# PowerBoard-v1_2.net
KiCad netlist of a schematic drawn in EAGLE
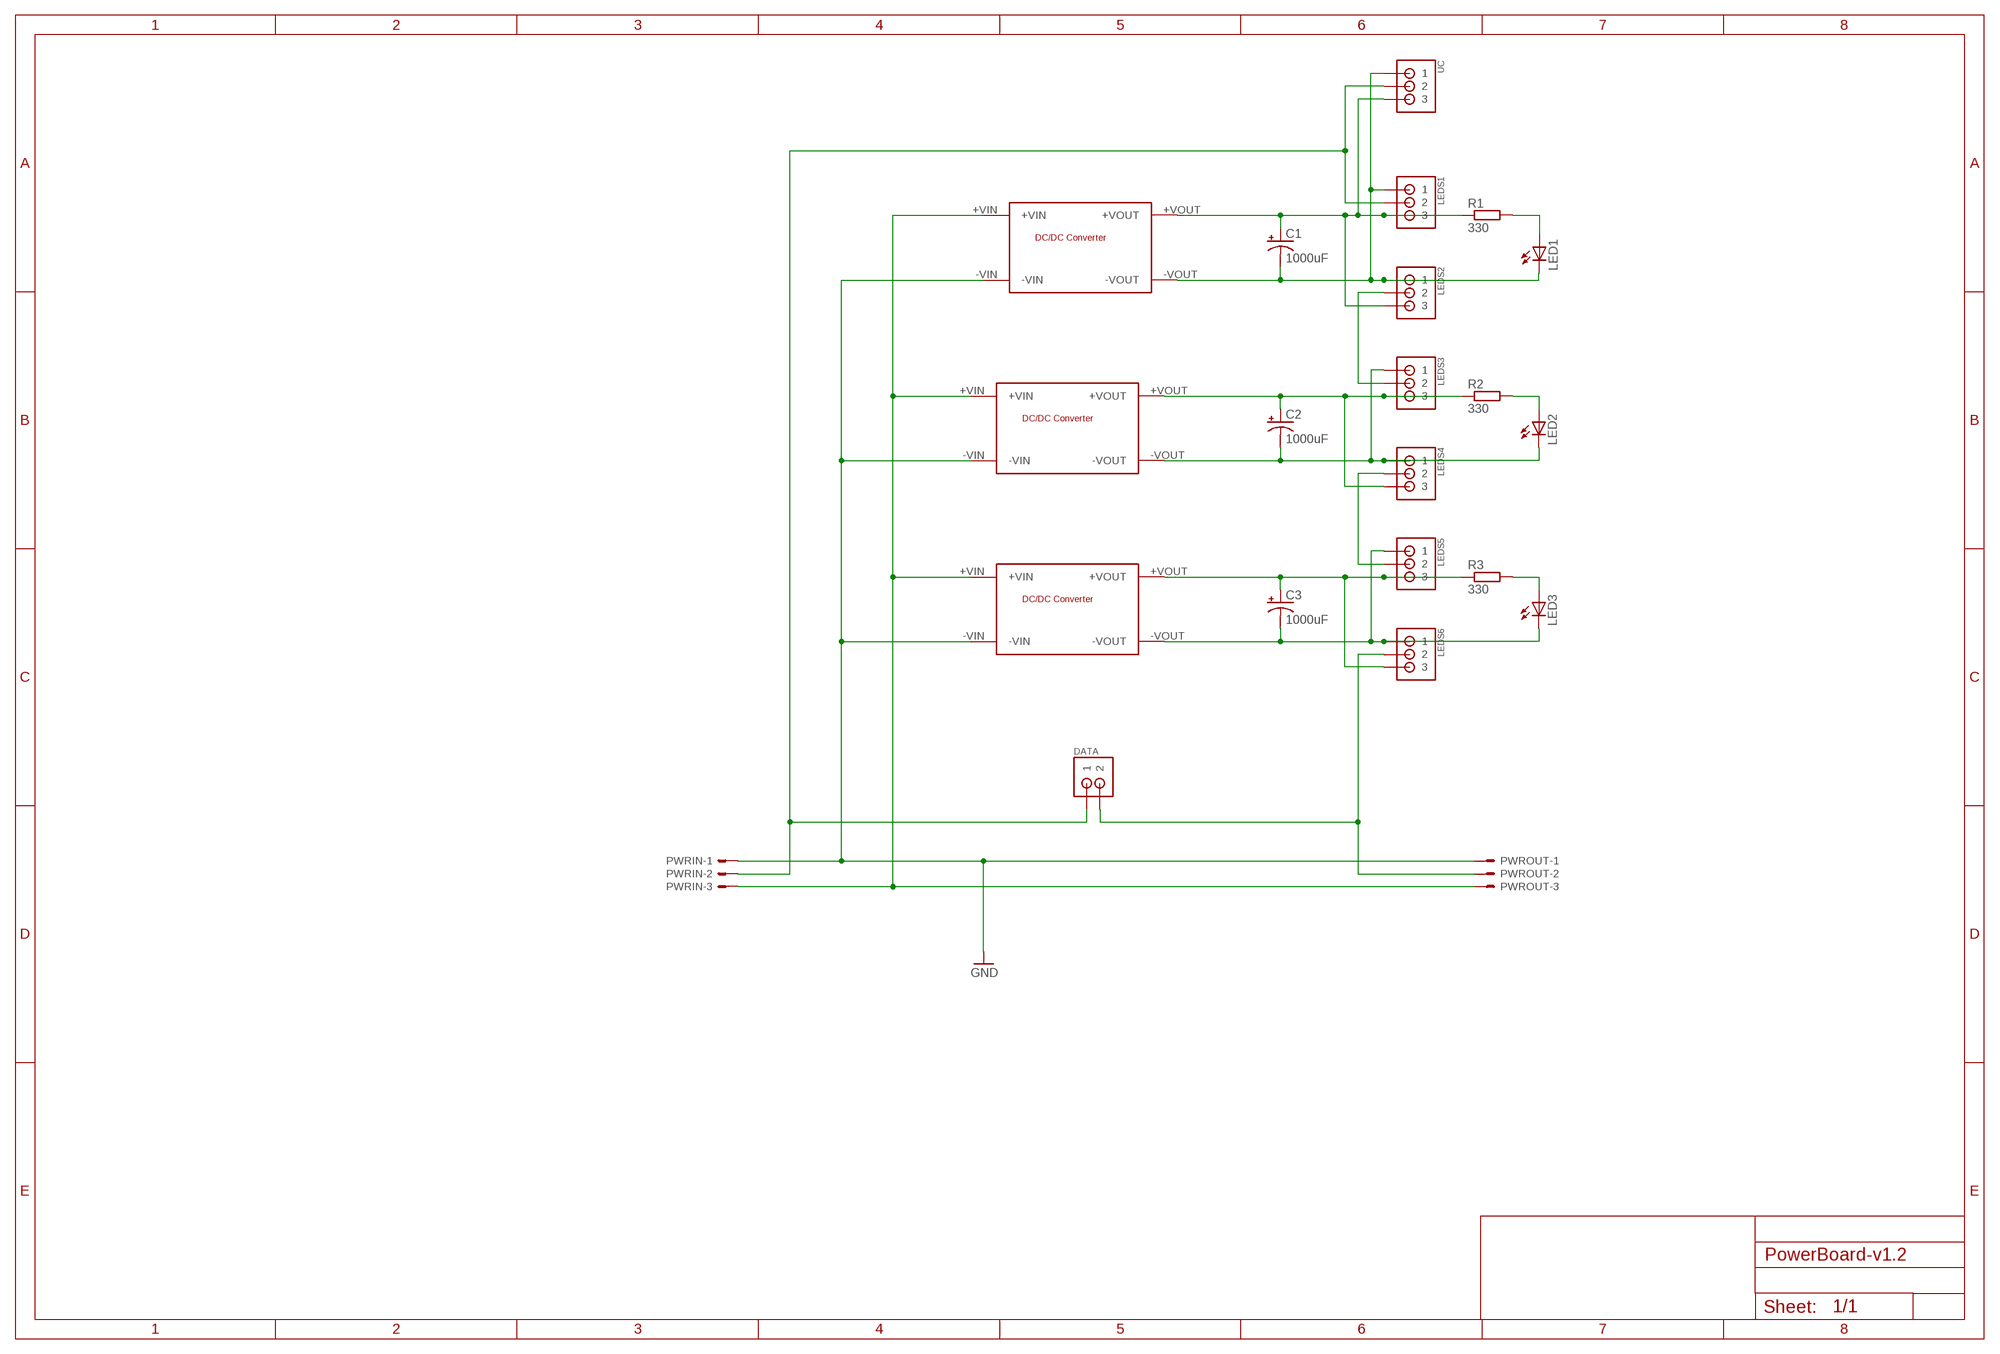
[diagram p0: schematic, sheet 1]

(export (version "E")
  (design (tool "Eeschema 10.0.6"))
  (components
    (comp (ref "C1")
      (value "1000uF")
      (footprint "eagle-import:CPOL-RADIAL-1000UF-25V")
      (libsource (lib "eagle-import") (part "CAP_POLPTH4"))
    )
    (comp (ref "C2")
      (value "1000uF")
      (footprint "eagle-import:CPOL-RADIAL-1000UF-25V")
      (libsource (lib "eagle-import") (part "CAP_POLPTH4"))
    )
    (comp (ref "C3")
      (value "1000uF")
      (footprint "eagle-import:CPOL-RADIAL-1000UF-25V")
      (libsource (lib "eagle-import") (part "CAP_POLPTH4"))
    )
    (comp (ref "DATA")
      (value "JST-XA-02-PIN")
      (footprint "eagle-import:JST-XA-02")
      (libsource (lib "eagle-import") (part "JST-XA-02-PIN"))
    )
    (comp (ref "LED1")
      (value "LEDCHIP-LED0805")
      (footprint "eagle-import:CHIP-LED0805")
      (libsource (lib "eagle-import") (part "LEDCHIP-LED0805"))
    )
    (comp (ref "LED2")
      (value "LEDCHIP-LED0805")
      (footprint "eagle-import:CHIP-LED0805")
      (libsource (lib "eagle-import") (part "LEDCHIP-LED0805"))
    )
    (comp (ref "LED3")
      (value "LEDCHIP-LED0805")
      (footprint "eagle-import:CHIP-LED0805")
      (libsource (lib "eagle-import") (part "LEDCHIP-LED0805"))
    )
    (comp (ref "LEDS1")
      (value "JST-XA-03-PIN")
      (footprint "eagle-import:JST-XA-03")
      (libsource (lib "eagle-import") (part "JST-XA-03-PIN"))
    )
    (comp (ref "LEDS2")
      (value "JST-XA-03-PIN")
      (footprint "eagle-import:JST-XA-03")
      (libsource (lib "eagle-import") (part "JST-XA-03-PIN"))
    )
    (comp (ref "LEDS3")
      (value "JST-XA-03-PIN")
      (footprint "eagle-import:JST-XA-03")
      (libsource (lib "eagle-import") (part "JST-XA-03-PIN"))
    )
    (comp (ref "LEDS4")
      (value "JST-XA-03-PIN")
      (footprint "eagle-import:JST-XA-03")
      (libsource (lib "eagle-import") (part "JST-XA-03-PIN"))
    )
    (comp (ref "LEDS5")
      (value "JST-XA-03-PIN")
      (footprint "eagle-import:JST-XA-03")
      (libsource (lib "eagle-import") (part "JST-XA-03-PIN"))
    )
    (comp (ref "LEDS6")
      (value "JST-XA-03-PIN")
      (footprint "eagle-import:JST-XA-03")
      (libsource (lib "eagle-import") (part "JST-XA-03-PIN"))
    )
    (comp (ref "PWRIN")
      (value "KK-156-3")
      (footprint "eagle-import:KK-156-3")
      (fields (field (name "MF") "MOLEX"))
      (libsource (lib "eagle-import") (part "KK-156-3"))
    )
    (comp (ref "PWROUT")
      (value "KK-156-3")
      (footprint "eagle-import:KK-156-3")
      (fields (field (name "MF") "MOLEX"))
      (libsource (lib "eagle-import") (part "KK-156-3"))
    )
    (comp (ref "R1")
      (value "330")
      (footprint "eagle-import:M0805")
      (libsource (lib "eagle-import") (part "RESISTORM0805"))
    )
    (comp (ref "R2")
      (value "330")
      (footprint "eagle-import:M0805")
      (libsource (lib "eagle-import") (part "RESISTORM0805"))
    )
    (comp (ref "R3")
      (value "330")
      (footprint "eagle-import:M0805")
      (libsource (lib "eagle-import") (part "RESISTORM0805"))
    )
    (comp (ref "U$1")
      (value "DC-DC-CONVERTER")
      (footprint "eagle-import:MP1584EN-BUCK-CONVERTER")
      (libsource (lib "eagle-import") (part "DC-DC-CONVERTER"))
    )
    (comp (ref "U$2")
      (value "DC-DC-CONVERTER")
      (footprint "eagle-import:MP1584EN-BUCK-CONVERTER")
      (libsource (lib "eagle-import") (part "DC-DC-CONVERTER"))
    )
    (comp (ref "U$3")
      (value "DC-DC-CONVERTER")
      (footprint "eagle-import:MP1584EN-BUCK-CONVERTER")
      (libsource (lib "eagle-import") (part "DC-DC-CONVERTER"))
    )
    (comp (ref "UC")
      (value "JST-XA-03-PIN")
      (footprint "eagle-import:JST-XA-03")
      (libsource (lib "eagle-import") (part "JST-XA-03-PIN"))
    )
  )
  (nets
    (net (code "1") (name "GND") (class "Default")
      (node (ref "PWRIN") (pin "1") (pinfunction "S_1") (pintype "passive"))
      (node (ref "PWROUT") (pin "1") (pinfunction "S_1") (pintype "passive"))
      (node (ref "U$1") (pin "-VIN") (pinfunction "-VIN_-VIN") (pintype "bidirectional"))
      (node (ref "U$2") (pin "-VIN") (pinfunction "-VIN_-VIN") (pintype "bidirectional"))
      (node (ref "U$3") (pin "-VIN") (pinfunction "-VIN_-VIN") (pintype "bidirectional"))
    )
    (net (code "2") (name "Net-(C1-Pad+)") (class "Default")
      (node (ref "C1") (pin "+") (pinfunction "+_+") (pintype "passive"))
      (node (ref "LEDS1") (pin "3") (pinfunction "3_3") (pintype "bidirectional"))
      (node (ref "LEDS2") (pin "3") (pinfunction "3_3") (pintype "bidirectional"))
      (node (ref "R1") (pin "1") (pinfunction "1_1") (pintype "passive"))
      (node (ref "U$1") (pin "+VOUT") (pinfunction "+VOUT_+VOUT") (pintype "bidirectional"))
      (node (ref "UC") (pin "3") (pinfunction "3_3") (pintype "bidirectional"))
    )
    (net (code "3") (name "Net-(C1-Pad-)") (class "Default")
      (node (ref "C1") (pin "-") (pinfunction "-_-") (pintype "passive"))
      (node (ref "LED1") (pin "C") (pinfunction "C_C") (pintype "passive"))
      (node (ref "LEDS1") (pin "1") (pinfunction "1_1") (pintype "bidirectional"))
      (node (ref "LEDS2") (pin "1") (pinfunction "1_1") (pintype "bidirectional"))
      (node (ref "U$1") (pin "-VOUT") (pinfunction "-VOUT_-VOUT") (pintype "bidirectional"))
      (node (ref "UC") (pin "1") (pinfunction "1_1") (pintype "bidirectional"))
    )
    (net (code "4") (name "Net-(C2-Pad+)") (class "Default")
      (node (ref "C2") (pin "+") (pinfunction "+_+") (pintype "passive"))
      (node (ref "LEDS3") (pin "3") (pinfunction "3_3") (pintype "bidirectional"))
      (node (ref "LEDS4") (pin "3") (pinfunction "3_3") (pintype "bidirectional"))
      (node (ref "R2") (pin "1") (pinfunction "1_1") (pintype "passive"))
      (node (ref "U$2") (pin "+VOUT") (pinfunction "+VOUT_+VOUT") (pintype "bidirectional"))
    )
    (net (code "5") (name "Net-(C2-Pad-)") (class "Default")
      (node (ref "C2") (pin "-") (pinfunction "-_-") (pintype "passive"))
      (node (ref "LED2") (pin "C") (pinfunction "C_C") (pintype "passive"))
      (node (ref "LEDS3") (pin "1") (pinfunction "1_1") (pintype "bidirectional"))
      (node (ref "LEDS4") (pin "1") (pinfunction "1_1") (pintype "bidirectional"))
      (node (ref "U$2") (pin "-VOUT") (pinfunction "-VOUT_-VOUT") (pintype "bidirectional"))
    )
    (net (code "6") (name "Net-(C3-Pad+)") (class "Default")
      (node (ref "C3") (pin "+") (pinfunction "+_+") (pintype "passive"))
      (node (ref "LEDS5") (pin "3") (pinfunction "3_3") (pintype "bidirectional"))
      (node (ref "LEDS6") (pin "3") (pinfunction "3_3") (pintype "bidirectional"))
      (node (ref "R3") (pin "1") (pinfunction "1_1") (pintype "passive"))
      (node (ref "U$3") (pin "+VOUT") (pinfunction "+VOUT_+VOUT") (pintype "bidirectional"))
    )
    (net (code "7") (name "Net-(C3-Pad-)") (class "Default")
      (node (ref "C3") (pin "-") (pinfunction "-_-") (pintype "passive"))
      (node (ref "LED3") (pin "C") (pinfunction "C_C") (pintype "passive"))
      (node (ref "LEDS5") (pin "1") (pinfunction "1_1") (pintype "bidirectional"))
      (node (ref "LEDS6") (pin "1") (pinfunction "1_1") (pintype "bidirectional"))
      (node (ref "U$3") (pin "-VOUT") (pinfunction "-VOUT_-VOUT") (pintype "bidirectional"))
    )
    (net (code "8") (name "Net-(LED1-PadA)") (class "Default")
      (node (ref "LED1") (pin "A") (pinfunction "A_A") (pintype "passive"))
      (node (ref "R1") (pin "2") (pinfunction "2_2") (pintype "passive"))
    )
    (net (code "9") (name "Net-(LED2-PadA)") (class "Default")
      (node (ref "LED2") (pin "A") (pinfunction "A_A") (pintype "passive"))
      (node (ref "R2") (pin "2") (pinfunction "2_2") (pintype "passive"))
    )
    (net (code "10") (name "Net-(LED3-PadA)") (class "Default")
      (node (ref "LED3") (pin "A") (pinfunction "A_A") (pintype "passive"))
      (node (ref "R3") (pin "2") (pinfunction "2_2") (pintype "passive"))
    )
    (net (code "11") (name "Net-(LEDS2-Pad2)") (class "Default")
      (node (ref "LEDS2") (pin "2") (pinfunction "2_2") (pintype "bidirectional"))
      (node (ref "LEDS3") (pin "2") (pinfunction "2_2") (pintype "bidirectional"))
    )
    (net (code "12") (name "Net-(LEDS4-Pad2)") (class "Default")
      (node (ref "LEDS4") (pin "2") (pinfunction "2_2") (pintype "bidirectional"))
      (node (ref "LEDS5") (pin "2") (pinfunction "2_2") (pintype "bidirectional"))
    )
    (net (code "13") (name "Net-(PWRINB-S)") (class "Default")
      (node (ref "DATA") (pin "1") (pinfunction "1_1") (pintype "bidirectional"))
      (node (ref "LEDS1") (pin "2") (pinfunction "2_2") (pintype "bidirectional"))
      (node (ref "PWRIN") (pin "2") (pinfunction "S_2") (pintype "passive"))
      (node (ref "UC") (pin "2") (pinfunction "2_2") (pintype "bidirectional"))
    )
    (net (code "14") (name "Net-(PWRINC-S)") (class "Default")
      (node (ref "PWRIN") (pin "3") (pinfunction "S_3") (pintype "passive"))
      (node (ref "PWROUT") (pin "3") (pinfunction "S_3") (pintype "passive"))
      (node (ref "U$1") (pin "+VIN") (pinfunction "+VIN_+VIN") (pintype "bidirectional"))
      (node (ref "U$2") (pin "+VIN") (pinfunction "+VIN_+VIN") (pintype "bidirectional"))
      (node (ref "U$3") (pin "+VIN") (pinfunction "+VIN_+VIN") (pintype "bidirectional"))
    )
    (net (code "15") (name "Net-(PWROUTB-S)") (class "Default")
      (node (ref "DATA") (pin "2") (pinfunction "2_2") (pintype "bidirectional"))
      (node (ref "LEDS6") (pin "2") (pinfunction "2_2") (pintype "bidirectional"))
      (node (ref "PWROUT") (pin "2") (pinfunction "S_2") (pintype "passive"))
    )
  )
)
